# TMC2660-test.net
KiCad netlist of a schematic drawn in EAGLE
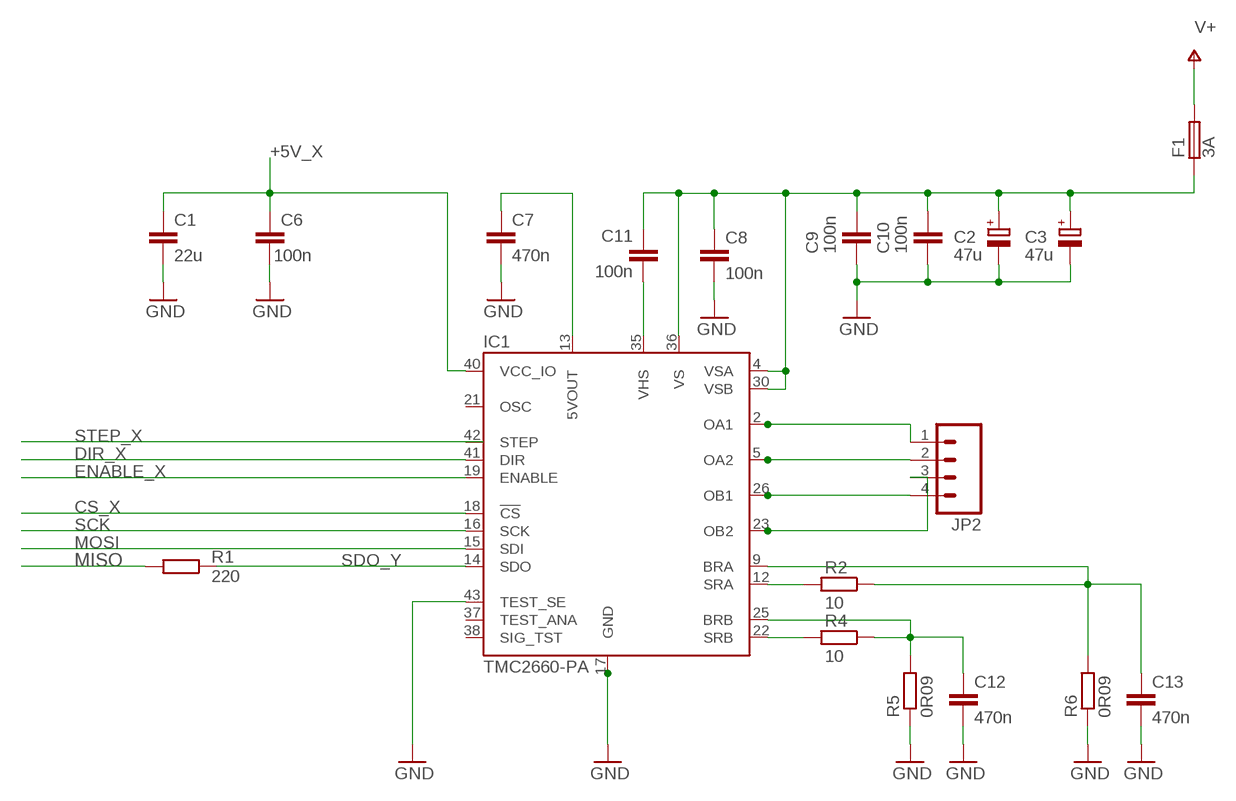
[diagram p0: schematic, sheet 1]
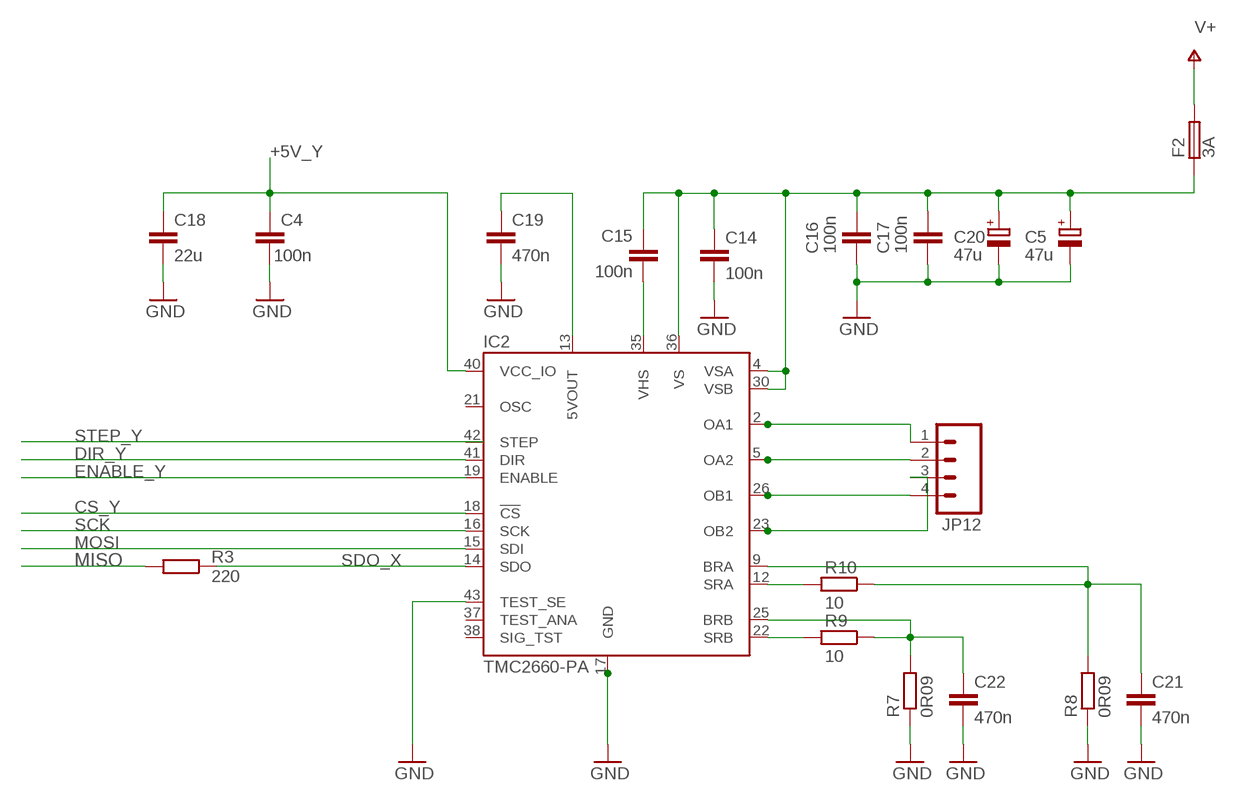
[diagram p1: schematic, sheet 2]
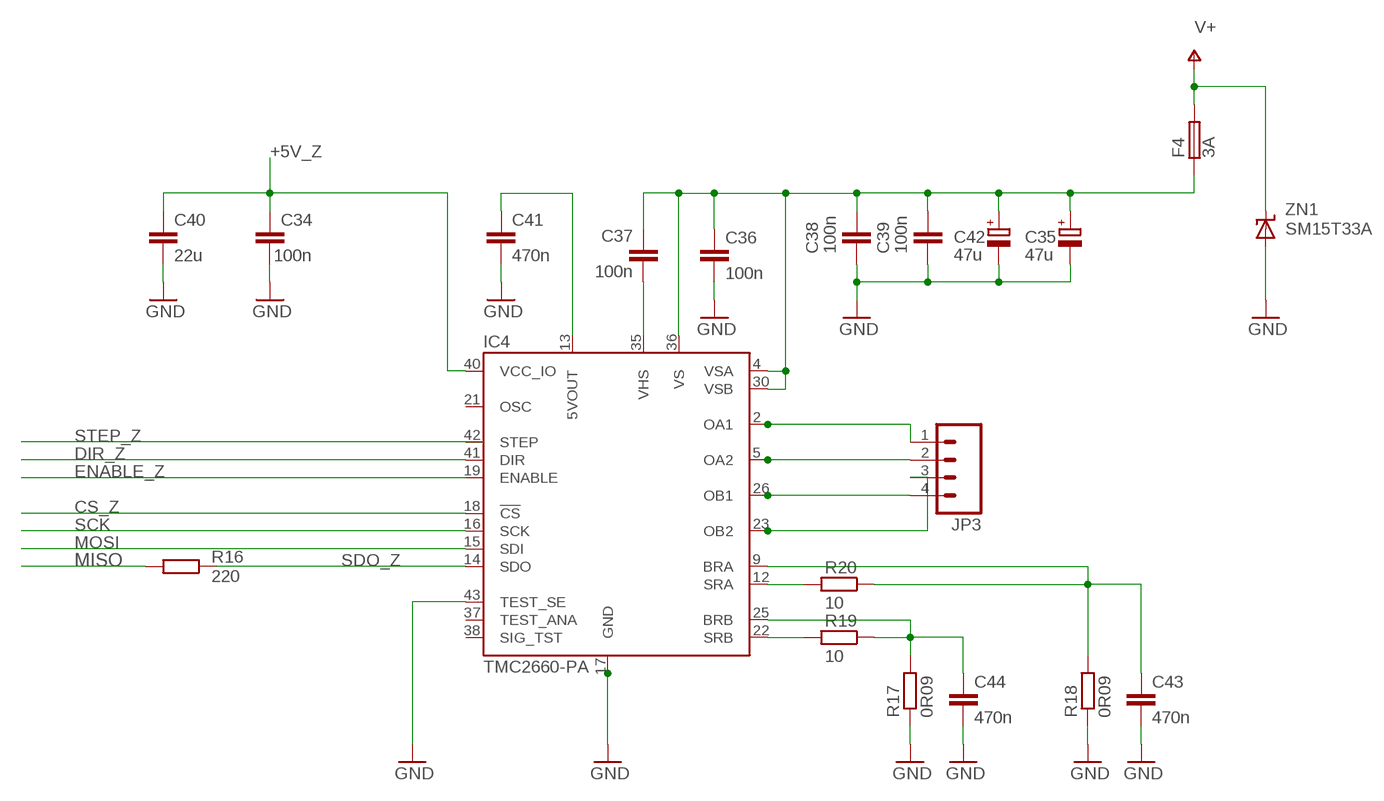
[diagram p2: schematic, sheet 3]
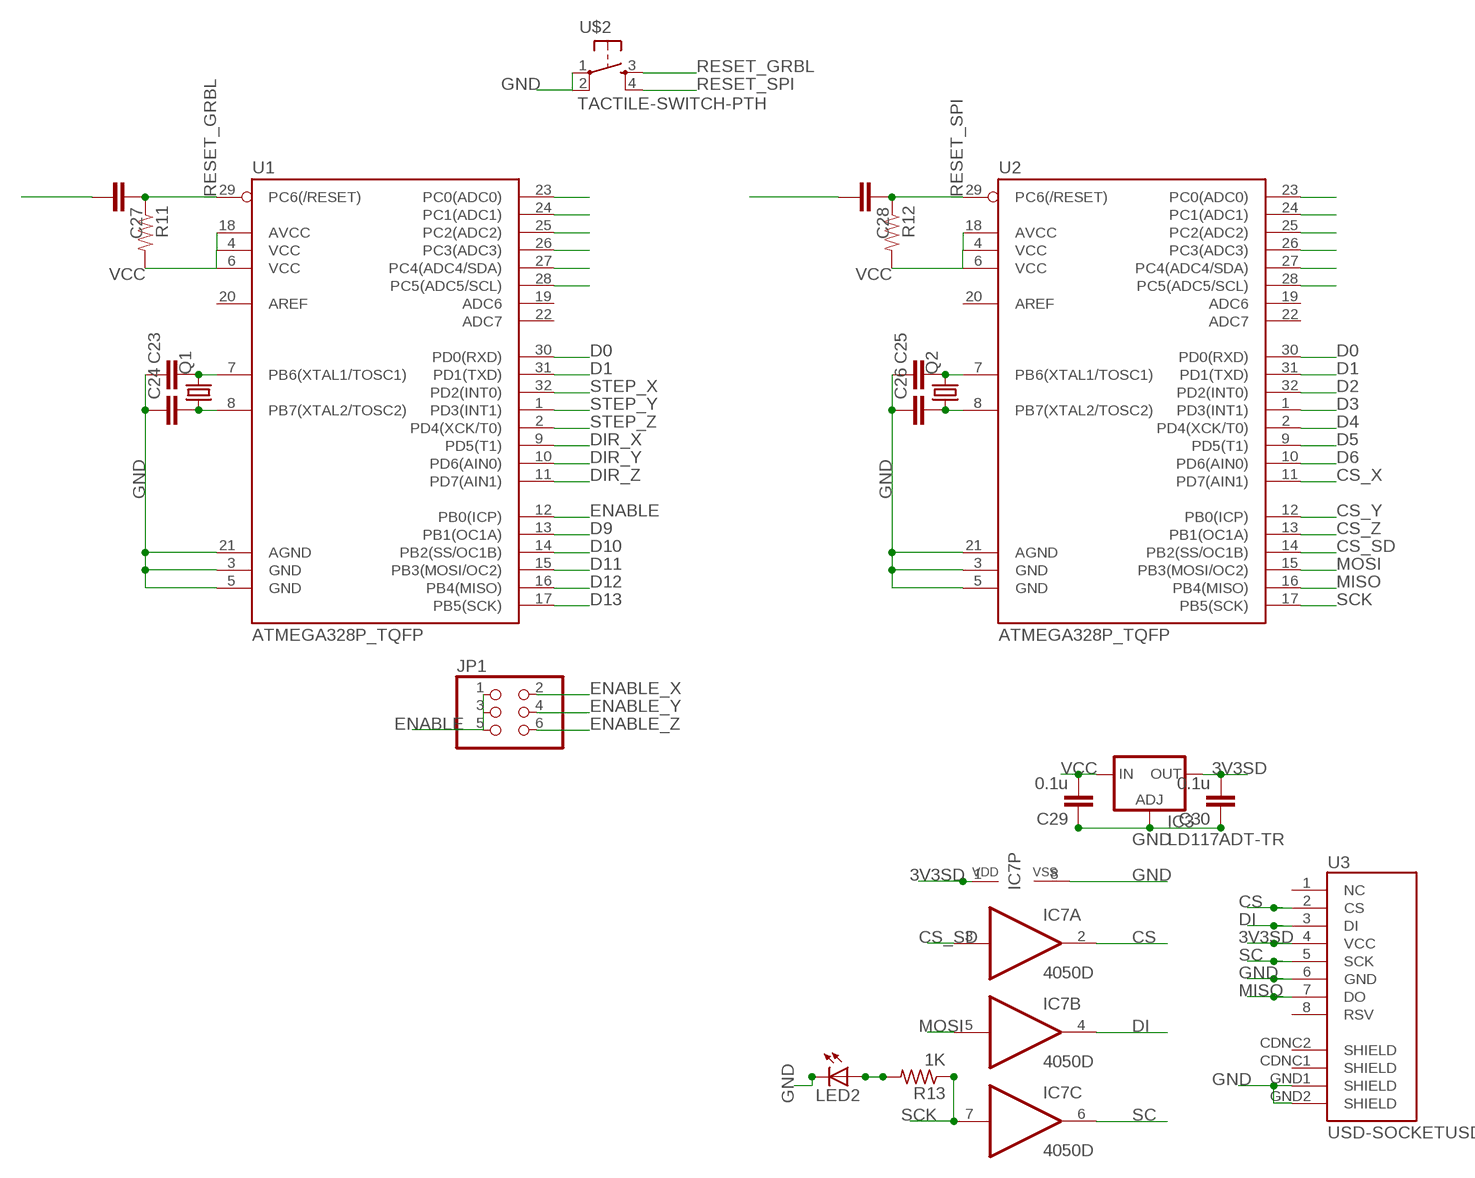
[diagram p3: schematic, sheet 4]

(export (version "E")
  (design (tool "Eeschema 10.0.6"))
  (components
    (comp (ref "C23")
      (value "CAP1206")
      (footprint "eagle-import:1206")
      (libsource (lib "eagle-import") (part "CAP1206"))
    )
    (comp (ref "C24")
      (value "CAP1206")
      (footprint "eagle-import:1206")
      (libsource (lib "eagle-import") (part "CAP1206"))
    )
    (comp (ref "C25")
      (value "CAP1206")
      (footprint "eagle-import:1206")
      (libsource (lib "eagle-import") (part "CAP1206"))
    )
    (comp (ref "C26")
      (value "CAP1206")
      (footprint "eagle-import:1206")
      (libsource (lib "eagle-import") (part "CAP1206"))
    )
    (comp (ref "C27")
      (value "CAP1206")
      (footprint "eagle-import:1206")
      (libsource (lib "eagle-import") (part "CAP1206"))
    )
    (comp (ref "C28")
      (value "CAP1206")
      (footprint "eagle-import:1206")
      (libsource (lib "eagle-import") (part "CAP1206"))
    )
    (comp (ref "C29")
      (value "0.1u")
      (footprint "eagle-import:1206")
      (libsource (lib "eagle-import") (part "SparkFun-Passives_CAP1206"))
    )
    (comp (ref "C30")
      (value "0.1u")
      (footprint "eagle-import:1206")
      (libsource (lib "eagle-import") (part "SparkFun-Passives_CAP1206"))
    )
    (comp (ref "IC3")
      (value "LD117ADT-TR")
      (footprint "eagle-import:DPACK")
      (libsource (lib "eagle-import") (part "LD117A?DT-TR"))
    )
    (comp (ref "IC7")
      (value "4050D")
      (footprint "eagle-import:SO16")
      (libsource (lib "eagle-import") (part "4050D"))
    )
    (comp (ref "JP1")
      (value "PINHD-2X3")
      (footprint "eagle-import:2X03")
      (libsource (lib "eagle-import") (part "PINHD-2X3"))
    )
    (comp (ref "LED2")
      (value "LEDSMT1206")
      (footprint "eagle-import:1206")
      (libsource (lib "eagle-import") (part "LEDSMT1206"))
    )
    (comp (ref "Q1")
      (value "CRYSTALHC49UP")
      (footprint "eagle-import:HC49UP")
      (libsource (lib "eagle-import") (part "CRYSTALHC49UP"))
    )
    (comp (ref "Q2")
      (value "CRYSTALHC49UP")
      (footprint "eagle-import:HC49UP")
      (libsource (lib "eagle-import") (part "CRYSTALHC49UP"))
    )
    (comp (ref "R11")
      (value "RESISTOR1206")
      (footprint "eagle-import:1206")
      (libsource (lib "eagle-import") (part "RESISTOR1206"))
    )
    (comp (ref "R12")
      (value "RESISTOR1206")
      (footprint "eagle-import:1206")
      (libsource (lib "eagle-import") (part "RESISTOR1206"))
    )
    (comp (ref "R13")
      (value "1K")
      (footprint "eagle-import:M1206")
      (libsource (lib "eagle-import") (part "R-US_M1206"))
    )
    (comp (ref "U$2")
      (value "TACTILE-SWITCH-PTH")
      (footprint "eagle-import:TAC-SWITCH-PTH")
      (libsource (lib "eagle-import") (part "TACTILE-SWITCH-PTH"))
    )
    (comp (ref "U1")
      (value "ATMEGA328P_TQFP")
      (footprint "eagle-import:TQFP32-08")
      (libsource (lib "eagle-import") (part "ATMEGA328P_TQFP"))
    )
    (comp (ref "U2")
      (value "ATMEGA328P_TQFP")
      (footprint "eagle-import:TQFP32-08")
      (libsource (lib "eagle-import") (part "ATMEGA328P_TQFP"))
    )
    (comp (ref "U3")
      (value "USD-SOCKETUSD")
      (footprint "eagle-import:USD-SOCKET-PP")
      (libsource (lib "eagle-import") (part "USD-SOCKETUSD"))
    )
    (comp (ref "C1")
      (value "22u")
      (footprint "eagle-import:C1206")
      (fields (field (name "MANUFACTURER") "Taiyo Yuden") (field (name "VOLTAGE") "6.3V"))
      (libsource (lib "eagle-import") (part "C-EUC1206"))
    )
    (comp (ref "C2")
      (value "47u")
      (footprint "eagle-import:E5-8,5")
      (fields (field (name "MANUFACTURER") "PANASONIC") (field (name "VOLTAGE") "50V"))
      (libsource (lib "eagle-import") (part "CPOL-EUE5-8.5"))
    )
    (comp (ref "C3")
      (value "47u")
      (footprint "eagle-import:E5-8,5")
      (fields (field (name "MANUFACTURER") "PANASONIC") (field (name "VOLTAGE") "50V"))
      (libsource (lib "eagle-import") (part "CPOL-EUE5-8.5"))
    )
    (comp (ref "C6")
      (value "100n")
      (footprint "eagle-import:C1206K")
      (fields (field (name "MANUFACTURER") "Kemet") (field (name "VOLTAGE") "25V"))
      (libsource (lib "eagle-import") (part "C-EUC1206K"))
    )
    (comp (ref "C7")
      (value "470n")
      (footprint "eagle-import:0805-WIDE")
      (fields (field (name "MANUFACTURER") "Vishay") (field (name "VOLTAGE") "10V"))
      (libsource (lib "eagle-import") (part "C-0805W"))
    )
    (comp (ref "C8")
      (value "100n")
      (footprint "eagle-import:C0603K")
      (fields (field (name "MANUFACTURER") "Kemet") (field (name "VOLTAGE") "50V"))
      (libsource (lib "eagle-import") (part "C-EUC0603K"))
    )
    (comp (ref "C9")
      (value "100n")
      (footprint "eagle-import:C0603K")
      (fields (field (name "MANUFACTURER") "Kemet") (field (name "VOLTAGE") "50V"))
      (libsource (lib "eagle-import") (part "C-EUC0603K"))
    )
    (comp (ref "C10")
      (value "100n")
      (footprint "eagle-import:C0603K")
      (fields (field (name "MANUFACTURER") "Kemet") (field (name "VOLTAGE") "50V"))
      (libsource (lib "eagle-import") (part "C-EUC0603K"))
    )
    (comp (ref "C11")
      (value "100n")
      (footprint "eagle-import:C0603K")
      (fields (field (name "MANUFACTURER") "Kemet") (field (name "VOLTAGE") "50V"))
      (libsource (lib "eagle-import") (part "C-EUC0603K"))
    )
    (comp (ref "C12")
      (value "470n")
      (footprint "eagle-import:0805-WIDE")
      (fields (field (name "MANUFACTURER") "Vishay") (field (name "VOLTAGE") "10V"))
      (libsource (lib "eagle-import") (part "C-0805W"))
    )
    (comp (ref "C13")
      (value "470n")
      (footprint "eagle-import:0805-WIDE")
      (fields (field (name "MANUFACTURER") "Vishay") (field (name "VOLTAGE") "10V"))
      (libsource (lib "eagle-import") (part "C-0805W"))
    )
    (comp (ref "F1")
      (value "3A")
      (footprint "eagle-import:AF2")
      (fields
        (field (name "MANUFACTURER") "AEM")
        (field (name "MANUFACTURER_1") "Cooper Bussman")
        (field (name "PARTNR") "CB61F3A-TR2")
        (field (name "VOLTAGE") "125V")
      )
      (libsource (lib "eagle-import") (part "AF2-FUSE_AF"))
    )
    (comp (ref "IC1")
      (value "TMC2660-PA")
      (footprint "eagle-import:PQFP44")
      (fields (field (name "MANUFACTURER") "TRINAMIC"))
      (libsource (lib "eagle-import") (part "TMC2660-PA"))
    )
    (comp (ref "JP2")
      (value "M04SCREW")
      (footprint "eagle-import:SCREWTERMINAL-3.5MM-4")
      (libsource (lib "eagle-import") (part "M04SCREW"))
    )
    (comp (ref "R1")
      (value "220")
      (footprint "eagle-import:R0603")
      (fields (field (name "MANUFACTURER") "KOA Speer"))
      (libsource (lib "eagle-import") (part "R-EU_R0603"))
    )
    (comp (ref "R2")
      (value "10")
      (footprint "eagle-import:R0603")
      (fields (field (name "MANUFACTURER") "KOA Speer"))
      (libsource (lib "eagle-import") (part "R-EU_R0603"))
    )
    (comp (ref "R4")
      (value "10")
      (footprint "eagle-import:R0603")
      (fields (field (name "MANUFACTURER") "KOA Speer"))
      (libsource (lib "eagle-import") (part "R-EU_R0603"))
    )
    (comp (ref "R5")
      (value "0R09")
      (footprint "eagle-import:R2512")
      (fields (field (name "MANUFACTURER") "Panasonic") (field (name "POWER") "0.75W"))
      (libsource (lib "eagle-import") (part "R-EU_R2512"))
    )
    (comp (ref "R6")
      (value "0R09")
      (footprint "eagle-import:R2512")
      (fields (field (name "MANUFACTURER") "Panasonic") (field (name "POWER") "0.75W"))
      (libsource (lib "eagle-import") (part "R-EU_R2512"))
    )
    (comp (ref "C34")
      (value "100n")
      (footprint "eagle-import:C1206K")
      (fields (field (name "MANUFACTURER") "Kemet") (field (name "VOLTAGE") "25V"))
      (libsource (lib "eagle-import") (part "C-EUC1206K"))
    )
    (comp (ref "C35")
      (value "47u")
      (footprint "eagle-import:E5-8,5")
      (fields (field (name "MANUFACTURER") "PANASONIC") (field (name "VOLTAGE") "50V"))
      (libsource (lib "eagle-import") (part "CPOL-EUE5-8.5"))
    )
    (comp (ref "C36")
      (value "100n")
      (footprint "eagle-import:C0603K")
      (fields (field (name "MANUFACTURER") "Kemet") (field (name "VOLTAGE") "50V"))
      (libsource (lib "eagle-import") (part "C-EUC0603K"))
    )
    (comp (ref "C37")
      (value "100n")
      (footprint "eagle-import:C0603K")
      (fields (field (name "MANUFACTURER") "Kemet") (field (name "VOLTAGE") "50V"))
      (libsource (lib "eagle-import") (part "C-EUC0603K"))
    )
    (comp (ref "C38")
      (value "100n")
      (footprint "eagle-import:C0603K")
      (fields (field (name "MANUFACTURER") "Kemet") (field (name "VOLTAGE") "50V"))
      (libsource (lib "eagle-import") (part "C-EUC0603K"))
    )
    (comp (ref "C39")
      (value "100n")
      (footprint "eagle-import:C0603K")
      (fields (field (name "MANUFACTURER") "Kemet") (field (name "VOLTAGE") "50V"))
      (libsource (lib "eagle-import") (part "C-EUC0603K"))
    )
    (comp (ref "C40")
      (value "22u")
      (footprint "eagle-import:C1206")
      (fields (field (name "MANUFACTURER") "Taiyo Yuden") (field (name "VOLTAGE") "6.3V"))
      (libsource (lib "eagle-import") (part "C-EUC1206"))
    )
    (comp (ref "C41")
      (value "470n")
      (footprint "eagle-import:0805-WIDE")
      (fields (field (name "MANUFACTURER") "Vishay") (field (name "VOLTAGE") "10V"))
      (libsource (lib "eagle-import") (part "C-0805W"))
    )
    (comp (ref "C42")
      (value "47u")
      (footprint "eagle-import:E5-8,5")
      (fields (field (name "MANUFACTURER") "PANASONIC") (field (name "VOLTAGE") "50V"))
      (libsource (lib "eagle-import") (part "CPOL-EUE5-8.5"))
    )
    (comp (ref "C43")
      (value "470n")
      (footprint "eagle-import:0805-WIDE")
      (fields (field (name "MANUFACTURER") "Vishay") (field (name "VOLTAGE") "10V"))
      (libsource (lib "eagle-import") (part "C-0805W"))
    )
    (comp (ref "C44")
      (value "470n")
      (footprint "eagle-import:0805-WIDE")
      (fields (field (name "MANUFACTURER") "Vishay") (field (name "VOLTAGE") "10V"))
      (libsource (lib "eagle-import") (part "C-0805W"))
    )
    (comp (ref "F4")
      (value "3A")
      (footprint "eagle-import:AF2")
      (fields
        (field (name "MANUFACTURER") "AEM")
        (field (name "MANUFACTURER_1") "Cooper Bussman")
        (field (name "PARTNR") "CB61F3A-TR2")
        (field (name "VOLTAGE") "125V")
      )
      (libsource (lib "eagle-import") (part "AF2-FUSE_AF"))
    )
    (comp (ref "IC4")
      (value "TMC2660-PA")
      (footprint "eagle-import:PQFP44")
      (fields (field (name "MANUFACTURER") "TRINAMIC"))
      (libsource (lib "eagle-import") (part "TMC2660-PA"))
    )
    (comp (ref "JP3")
      (value "M04SCREW")
      (footprint "eagle-import:SCREWTERMINAL-3.5MM-4")
      (libsource (lib "eagle-import") (part "M04SCREW"))
    )
    (comp (ref "R16")
      (value "220")
      (footprint "eagle-import:R0603")
      (fields (field (name "MANUFACTURER") "KOA Speer"))
      (libsource (lib "eagle-import") (part "R-EU_R0603"))
    )
    (comp (ref "R17")
      (value "0R09")
      (footprint "eagle-import:R2512")
      (fields (field (name "MANUFACTURER") "Panasonic") (field (name "POWER") "0.75W"))
      (libsource (lib "eagle-import") (part "R-EU_R2512"))
    )
    (comp (ref "R18")
      (value "0R09")
      (footprint "eagle-import:R2512")
      (fields (field (name "MANUFACTURER") "Panasonic") (field (name "POWER") "0.75W"))
      (libsource (lib "eagle-import") (part "R-EU_R2512"))
    )
    (comp (ref "R19")
      (value "10")
      (footprint "eagle-import:R0603")
      (fields (field (name "MANUFACTURER") "KOA Speer"))
      (libsource (lib "eagle-import") (part "R-EU_R0603"))
    )
    (comp (ref "R20")
      (value "10")
      (footprint "eagle-import:R0603")
      (fields (field (name "MANUFACTURER") "KOA Speer"))
      (libsource (lib "eagle-import") (part "R-EU_R0603"))
    )
    (comp (ref "ZN1")
      (value "SM15T33A")
      (footprint "eagle-import:SMC")
      (fields (field (name "MANUFACTURER") "ST"))
      (libsource (lib "eagle-import") (part "D-ZN_SMC"))
    )
    (comp (ref "C4")
      (value "100n")
      (footprint "eagle-import:C1206K")
      (fields (field (name "MANUFACTURER") "Kemet") (field (name "VOLTAGE") "25V"))
      (libsource (lib "eagle-import") (part "C-EUC1206K"))
    )
    (comp (ref "C5")
      (value "47u")
      (footprint "eagle-import:E5-8,5")
      (fields (field (name "MANUFACTURER") "PANASONIC") (field (name "VOLTAGE") "50V"))
      (libsource (lib "eagle-import") (part "CPOL-EUE5-8.5"))
    )
    (comp (ref "C14")
      (value "100n")
      (footprint "eagle-import:C0603K")
      (fields (field (name "MANUFACTURER") "Kemet") (field (name "VOLTAGE") "50V"))
      (libsource (lib "eagle-import") (part "C-EUC0603K"))
    )
    (comp (ref "C15")
      (value "100n")
      (footprint "eagle-import:C0603K")
      (fields (field (name "MANUFACTURER") "Kemet") (field (name "VOLTAGE") "50V"))
      (libsource (lib "eagle-import") (part "C-EUC0603K"))
    )
    (comp (ref "C16")
      (value "100n")
      (footprint "eagle-import:C0603K")
      (fields (field (name "MANUFACTURER") "Kemet") (field (name "VOLTAGE") "50V"))
      (libsource (lib "eagle-import") (part "C-EUC0603K"))
    )
    (comp (ref "C17")
      (value "100n")
      (footprint "eagle-import:C0603K")
      (fields (field (name "MANUFACTURER") "Kemet") (field (name "VOLTAGE") "50V"))
      (libsource (lib "eagle-import") (part "C-EUC0603K"))
    )
    (comp (ref "C18")
      (value "22u")
      (footprint "eagle-import:C1206")
      (fields (field (name "MANUFACTURER") "Taiyo Yuden") (field (name "VOLTAGE") "6.3V"))
      (libsource (lib "eagle-import") (part "C-EUC1206"))
    )
    (comp (ref "C19")
      (value "470n")
      (footprint "eagle-import:0805-WIDE")
      (fields (field (name "MANUFACTURER") "Vishay") (field (name "VOLTAGE") "10V"))
      (libsource (lib "eagle-import") (part "C-0805W"))
    )
    (comp (ref "C20")
      (value "47u")
      (footprint "eagle-import:E5-8,5")
      (fields (field (name "MANUFACTURER") "PANASONIC") (field (name "VOLTAGE") "50V"))
      (libsource (lib "eagle-import") (part "CPOL-EUE5-8.5"))
    )
    (comp (ref "C21")
      (value "470n")
      (footprint "eagle-import:0805-WIDE")
      (fields (field (name "MANUFACTURER") "Vishay") (field (name "VOLTAGE") "10V"))
      (libsource (lib "eagle-import") (part "C-0805W"))
    )
    (comp (ref "C22")
      (value "470n")
      (footprint "eagle-import:0805-WIDE")
      (fields (field (name "MANUFACTURER") "Vishay") (field (name "VOLTAGE") "10V"))
      (libsource (lib "eagle-import") (part "C-0805W"))
    )
    (comp (ref "F2")
      (value "3A")
      (footprint "eagle-import:AF2")
      (fields
        (field (name "MANUFACTURER") "AEM")
        (field (name "MANUFACTURER_1") "Cooper Bussman")
        (field (name "PARTNR") "CB61F3A-TR2")
        (field (name "VOLTAGE") "125V")
      )
      (libsource (lib "eagle-import") (part "AF2-FUSE_AF"))
    )
    (comp (ref "IC2")
      (value "TMC2660-PA")
      (footprint "eagle-import:PQFP44")
      (fields (field (name "MANUFACTURER") "TRINAMIC"))
      (libsource (lib "eagle-import") (part "TMC2660-PA"))
    )
    (comp (ref "JP12")
      (value "M04SCREW")
      (footprint "eagle-import:SCREWTERMINAL-3.5MM-4")
      (libsource (lib "eagle-import") (part "M04SCREW"))
    )
    (comp (ref "R3")
      (value "220")
      (footprint "eagle-import:R0603")
      (fields (field (name "MANUFACTURER") "KOA Speer"))
      (libsource (lib "eagle-import") (part "R-EU_R0603"))
    )
    (comp (ref "R7")
      (value "0R09")
      (footprint "eagle-import:R2512")
      (fields (field (name "MANUFACTURER") "Panasonic") (field (name "POWER") "0.75W"))
      (libsource (lib "eagle-import") (part "R-EU_R2512"))
    )
    (comp (ref "R8")
      (value "0R09")
      (footprint "eagle-import:R2512")
      (fields (field (name "MANUFACTURER") "Panasonic") (field (name "POWER") "0.75W"))
      (libsource (lib "eagle-import") (part "R-EU_R2512"))
    )
    (comp (ref "R9")
      (value "10")
      (footprint "eagle-import:R0603")
      (fields (field (name "MANUFACTURER") "KOA Speer"))
      (libsource (lib "eagle-import") (part "R-EU_R0603"))
    )
    (comp (ref "R10")
      (value "10")
      (footprint "eagle-import:R0603")
      (fields (field (name "MANUFACTURER") "KOA Speer"))
      (libsource (lib "eagle-import") (part "R-EU_R0603"))
    )
  )
  (nets
    (net (code "1") (name "+5V_X") (class "Default")
      (node (ref "C1") (pin "1") (pinfunction "1_1") (pintype "passive"))
      (node (ref "C6") (pin "2") (pinfunction "2_2") (pintype "passive"))
      (node (ref "IC1") (pin "40") (pinfunction "VCC_IO_40") (pintype "bidirectional"))
    )
    (net (code "2") (name "+5V_Y") (class "Default")
      (node (ref "C18") (pin "1") (pinfunction "1_1") (pintype "passive"))
      (node (ref "C4") (pin "2") (pinfunction "2_2") (pintype "passive"))
      (node (ref "IC2") (pin "40") (pinfunction "VCC_IO_40") (pintype "bidirectional"))
    )
    (net (code "3") (name "+5V_Z") (class "Default")
      (node (ref "C34") (pin "2") (pinfunction "2_2") (pintype "passive"))
      (node (ref "C40") (pin "1") (pinfunction "1_1") (pintype "passive"))
      (node (ref "IC4") (pin "40") (pinfunction "VCC_IO_40") (pintype "bidirectional"))
    )
    (net (code "4") (name "3V3SD") (class "Default")
      (node (ref "C30") (pin "2") (pinfunction "2_2") (pintype "passive"))
      (node (ref "IC3") (pin "4") (pinfunction "OUT_4") (pintype "passive"))
      (node (ref "IC7") (pin "1") (pinfunction "VDD_1") (pintype "power_in"))
      (node (ref "U3") (pin "4") (pinfunction "VCC_4") (pintype "bidirectional"))
    )
    (net (code "5") (name "CS") (class "Default")
      (node (ref "IC7") (pin "2") (pinfunction "O_2") (pintype "output"))
      (node (ref "U3") (pin "2") (pinfunction "CS_2") (pintype "bidirectional"))
    )
    (net (code "6") (name "CS_SD") (class "Default")
      (node (ref "IC7") (pin "3") (pinfunction "I_3") (pintype "input"))
      (node (ref "U2") (pin "14") (pinfunction "PB2(SS/OC1B)_14") (pintype "bidirectional"))
    )
    (net (code "7") (name "CS_X") (class "Default")
      (node (ref "IC1") (pin "18") (pinfunction "~{CS}_18") (pintype "bidirectional"))
      (node (ref "U2") (pin "11") (pinfunction "PD7(AIN1)_11") (pintype "bidirectional"))
    )
    (net (code "8") (name "CS_Y") (class "Default")
      (node (ref "IC2") (pin "18") (pinfunction "~{CS}_18") (pintype "bidirectional"))
      (node (ref "U2") (pin "12") (pinfunction "PB0(ICP)_12") (pintype "bidirectional"))
    )
    (net (code "9") (name "CS_Z") (class "Default")
      (node (ref "IC4") (pin "18") (pinfunction "~{CS}_18") (pintype "bidirectional"))
      (node (ref "U2") (pin "13") (pinfunction "PB1(OC1A)_13") (pintype "bidirectional"))
    )
    (net (code "10") (name "D0") (class "Default")
      (node (ref "U1") (pin "30") (pinfunction "PD0(RXD)_30") (pintype "bidirectional"))
      (node (ref "U2") (pin "30") (pinfunction "PD0(RXD)_30") (pintype "bidirectional"))
    )
    (net (code "11") (name "D1") (class "Default")
      (node (ref "U1") (pin "31") (pinfunction "PD1(TXD)_31") (pintype "bidirectional"))
      (node (ref "U2") (pin "31") (pinfunction "PD1(TXD)_31") (pintype "bidirectional"))
    )
    (net (code "12") (name "D2") (class "Default")
      (node (ref "U2") (pin "32") (pinfunction "PD2(INT0)_32") (pintype "bidirectional"))
    )
    (net (code "13") (name "D3") (class "Default")
      (node (ref "U2") (pin "1") (pinfunction "PD3(INT1)_1") (pintype "bidirectional"))
    )
    (net (code "14") (name "D4") (class "Default")
      (node (ref "U2") (pin "2") (pinfunction "PD4(XCK/T0)_2") (pintype "bidirectional"))
    )
    (net (code "15") (name "D5") (class "Default")
      (node (ref "U2") (pin "9") (pinfunction "PD5(T1)_9") (pintype "bidirectional"))
    )
    (net (code "16") (name "D6") (class "Default")
      (node (ref "U2") (pin "10") (pinfunction "PD6(AIN0)_10") (pintype "bidirectional"))
    )
    (net (code "17") (name "D9") (class "Default")
      (node (ref "U1") (pin "13") (pinfunction "PB1(OC1A)_13") (pintype "bidirectional"))
    )
    (net (code "18") (name "D10") (class "Default")
      (node (ref "U1") (pin "14") (pinfunction "PB2(SS/OC1B)_14") (pintype "bidirectional"))
    )
    (net (code "19") (name "D11") (class "Default")
      (node (ref "U1") (pin "15") (pinfunction "PB3(MOSI/OC2)_15") (pintype "bidirectional"))
    )
    (net (code "20") (name "D12") (class "Default")
      (node (ref "U1") (pin "16") (pinfunction "PB4(MISO)_16") (pintype "bidirectional"))
    )
    (net (code "21") (name "D13") (class "Default")
      (node (ref "U1") (pin "17") (pinfunction "PB5(SCK)_17") (pintype "bidirectional"))
    )
    (net (code "22") (name "DI") (class "Default")
      (node (ref "IC7") (pin "4") (pinfunction "O_4") (pintype "output"))
      (node (ref "U3") (pin "3") (pinfunction "DI_3") (pintype "bidirectional"))
    )
    (net (code "23") (name "DIR_X") (class "Default")
      (node (ref "IC1") (pin "41") (pinfunction "DIR_41") (pintype "bidirectional"))
      (node (ref "U1") (pin "9") (pinfunction "PD5(T1)_9") (pintype "bidirectional"))
    )
    (net (code "24") (name "DIR_Y") (class "Default")
      (node (ref "IC2") (pin "41") (pinfunction "DIR_41") (pintype "bidirectional"))
      (node (ref "U1") (pin "10") (pinfunction "PD6(AIN0)_10") (pintype "bidirectional"))
    )
    (net (code "25") (name "DIR_Z") (class "Default")
      (node (ref "IC4") (pin "41") (pinfunction "DIR_41") (pintype "bidirectional"))
      (node (ref "U1") (pin "11") (pinfunction "PD7(AIN1)_11") (pintype "bidirectional"))
    )
    (net (code "26") (name "ENABLE") (class "Default")
      (node (ref "JP1") (pin "1") (pinfunction "1_1") (pintype "passive"))
      (node (ref "JP1") (pin "3") (pinfunction "3_3") (pintype "passive"))
      (node (ref "JP1") (pin "5") (pinfunction "5_5") (pintype "passive"))
      (node (ref "U1") (pin "12") (pinfunction "PB0(ICP)_12") (pintype "bidirectional"))
    )
    (net (code "27") (name "ENABLE_X") (class "Default")
      (node (ref "IC1") (pin "19") (pinfunction "ENABLE_19") (pintype "bidirectional"))
      (node (ref "JP1") (pin "2") (pinfunction "2_2") (pintype "passive"))
    )
    (net (code "28") (name "ENABLE_Y") (class "Default")
      (node (ref "IC2") (pin "19") (pinfunction "ENABLE_19") (pintype "bidirectional"))
      (node (ref "JP1") (pin "4") (pinfunction "4_4") (pintype "passive"))
    )
    (net (code "29") (name "ENABLE_Z") (class "Default")
      (node (ref "IC4") (pin "19") (pinfunction "ENABLE_19") (pintype "bidirectional"))
      (node (ref "JP1") (pin "6") (pinfunction "6_6") (pintype "passive"))
    )
    (net (code "30") (name "GND") (class "Default")
      (node (ref "C1") (pin "2") (pinfunction "2_2") (pintype "passive"))
      (node (ref "C10") (pin "1") (pinfunction "1_1") (pintype "passive"))
      (node (ref "C12") (pin "2") (pinfunction "2_2") (pintype "passive"))
      (node (ref "C13") (pin "2") (pinfunction "2_2") (pintype "passive"))
      (node (ref "C14") (pin "2") (pinfunction "2_2") (pintype "passive"))
      (node (ref "C16") (pin "1") (pinfunction "1_1") (pintype "passive"))
      (node (ref "C17") (pin "1") (pinfunction "1_1") (pintype "passive"))
      (node (ref "C18") (pin "2") (pinfunction "2_2") (pintype "passive"))
      (node (ref "C19") (pin "2") (pinfunction "2_2") (pintype "passive"))
      (node (ref "C2") (pin "-") (pinfunction "-_-") (pintype "passive"))
      (node (ref "C20") (pin "-") (pinfunction "-_-") (pintype "passive"))
      (node (ref "C21") (pin "2") (pinfunction "2_2") (pintype "passive"))
      (node (ref "C22") (pin "2") (pinfunction "2_2") (pintype "passive"))
      (node (ref "C23") (pin "1") (pinfunction "1_1") (pintype "passive"))
      (node (ref "C24") (pin "1") (pinfunction "1_1") (pintype "passive"))
      (node (ref "C25") (pin "1") (pinfunction "1_1") (pintype "passive"))
      (node (ref "C26") (pin "1") (pinfunction "1_1") (pintype "passive"))
      (node (ref "C29") (pin "1") (pinfunction "1_1") (pintype "passive"))
      (node (ref "C3") (pin "-") (pinfunction "-_-") (pintype "passive"))
      (node (ref "C30") (pin "1") (pinfunction "1_1") (pintype "passive"))
      (node (ref "C34") (pin "1") (pinfunction "1_1") (pintype "passive"))
      (node (ref "C35") (pin "-") (pinfunction "-_-") (pintype "passive"))
      (node (ref "C36") (pin "2") (pinfunction "2_2") (pintype "passive"))
      (node (ref "C38") (pin "1") (pinfunction "1_1") (pintype "passive"))
      (node (ref "C39") (pin "1") (pinfunction "1_1") (pintype "passive"))
      (node (ref "C4") (pin "1") (pinfunction "1_1") (pintype "passive"))
      (node (ref "C40") (pin "2") (pinfunction "2_2") (pintype "passive"))
      (node (ref "C41") (pin "2") (pinfunction "2_2") (pintype "passive"))
      (node (ref "C42") (pin "-") (pinfunction "-_-") (pintype "passive"))
      (node (ref "C43") (pin "2") (pinfunction "2_2") (pintype "passive"))
      (node (ref "C44") (pin "2") (pinfunction "2_2") (pintype "passive"))
      (node (ref "C5") (pin "-") (pinfunction "-_-") (pintype "passive"))
      (node (ref "C6") (pin "1") (pinfunction "1_1") (pintype "passive"))
      (node (ref "C7") (pin "2") (pinfunction "2_2") (pintype "passive"))
      (node (ref "C8") (pin "2") (pinfunction "2_2") (pintype "passive"))
      (node (ref "C9") (pin "1") (pinfunction "1_1") (pintype "passive"))
      (node (ref "IC1") (pin "17") (pinfunction "GND_17") (pintype "bidirectional"))
      (node (ref "IC1") (pin "39") (pinfunction "GND1_39") (pintype "bidirectional"))
      (node (ref "IC1") (pin "43") (pinfunction "TEST_SE_43") (pintype "bidirectional"))
      (node (ref "IC1") (pin "44") (pinfunction "GND2_44") (pintype "bidirectional"))
      (node (ref "IC2") (pin "17") (pinfunction "GND_17") (pintype "bidirectional"))
      (node (ref "IC2") (pin "39") (pinfunction "GND1_39") (pintype "bidirectional"))
      (node (ref "IC2") (pin "43") (pinfunction "TEST_SE_43") (pintype "bidirectional"))
      (node (ref "IC2") (pin "44") (pinfunction "GND2_44") (pintype "bidirectional"))
      (node (ref "IC3") (pin "1") (pinfunction "ADJ_1") (pintype "input"))
      (node (ref "IC4") (pin "17") (pinfunction "GND_17") (pintype "bidirectional"))
      (node (ref "IC4") (pin "39") (pinfunction "GND1_39") (pintype "bidirectional"))
      (node (ref "IC4") (pin "43") (pinfunction "TEST_SE_43") (pintype "bidirectional"))
      (node (ref "IC4") (pin "44") (pinfunction "GND2_44") (pintype "bidirectional"))
      (node (ref "IC7") (pin "8") (pinfunction "VSS_8") (pintype "power_in"))
      (node (ref "LED2") (pin "C") (pinfunction "C_C") (pintype "passive"))
      (node (ref "R17") (pin "1") (pinfunction "1_1") (pintype "passive"))
      (node (ref "R18") (pin "1") (pinfunction "1_1") (pintype "passive"))
      (node (ref "R5") (pin "1") (pinfunction "1_1") (pintype "passive"))
      (node (ref "R6") (pin "1") (pinfunction "1_1") (pintype "passive"))
      (node (ref "R7") (pin "1") (pinfunction "1_1") (pintype "passive"))
      (node (ref "R8") (pin "1") (pinfunction "1_1") (pintype "passive"))
      (node (ref "U$2") (pin "1") (pinfunction "1_1") (pintype "passive"))
      (node (ref "U$2") (pin "2") (pinfunction "2_2") (pintype "passive"))
      (node (ref "U1") (pin "21") (pinfunction "AGND_21") (pintype "bidirectional"))
      (node (ref "U1") (pin "3") (pinfunction "GND_3") (pintype "bidirectional"))
      (node (ref "U1") (pin "5") (pinfunction "GND_5") (pintype "bidirectional"))
      (node (ref "U2") (pin "21") (pinfunction "AGND_21") (pintype "bidirectional"))
      (node (ref "U2") (pin "3") (pinfunction "GND_3") (pintype "bidirectional"))
      (node (ref "U2") (pin "5") (pinfunction "GND_5") (pintype "bidirectional"))
      (node (ref "U3") (pin "6") (pinfunction "GND_6") (pintype "bidirectional"))
      (node (ref "U3") (pin "GND1") (pinfunction "SHIELD_GND1") (pintype "bidirectional"))
      (node (ref "U3") (pin "GND2") (pinfunction "SHIELD_GND2") (pintype "bidirectional"))
      (node (ref "ZN1") (pin "P$2") (pinfunction "A_P$2") (pintype "passive"))
    )
    (net (code "31") (name "MISO") (class "Default")
      (node (ref "R1") (pin "2") (pinfunction "2_2") (pintype "passive"))
      (node (ref "R16") (pin "2") (pinfunction "2_2") (pintype "passive"))
      (node (ref "R3") (pin "2") (pinfunction "2_2") (pintype "passive"))
      (node (ref "U2") (pin "16") (pinfunction "PB4(MISO)_16") (pintype "bidirectional"))
      (node (ref "U3") (pin "7") (pinfunction "DO_7") (pintype "bidirectional"))
    )
    (net (code "32") (name "MOSI") (class "Default")
      (node (ref "IC1") (pin "15") (pinfunction "SDI_15") (pintype "bidirectional"))
      (node (ref "IC2") (pin "15") (pinfunction "SDI_15") (pintype "bidirectional"))
      (node (ref "IC4") (pin "15") (pinfunction "SDI_15") (pintype "bidirectional"))
      (node (ref "IC7") (pin "5") (pinfunction "I_5") (pintype "input"))
      (node (ref "U2") (pin "15") (pinfunction "PB3(MOSI/OC2)_15") (pintype "bidirectional"))
    )
    (net (code "33") (name "Net-(F1-1)") (class "Default")
      (node (ref "C10") (pin "2") (pinfunction "2_2") (pintype "passive"))
      (node (ref "C11") (pin "2") (pinfunction "2_2") (pintype "passive"))
      (node (ref "C2") (pin "+") (pinfunction "+_+") (pintype "passive"))
      (node (ref "C3") (pin "+") (pinfunction "+_+") (pintype "passive"))
      (node (ref "C8") (pin "1") (pinfunction "1_1") (pintype "passive"))
      (node (ref "C9") (pin "2") (pinfunction "2_2") (pintype "passive"))
      (node (ref "F1") (pin "P$1") (pinfunction "1_P$1") (pintype "passive"))
      (node (ref "IC1") (pin "30") (pinfunction "VSB_30") (pintype "bidirectional"))
      (node (ref "IC1") (pin "36") (pinfunction "VS_36") (pintype "bidirectional"))
      (node (ref "IC1") (pin "4") (pinfunction "VSA_4") (pintype "bidirectional"))
    )
    (net (code "34") (name "Net-(F2-1)") (class "Default")
      (node (ref "C14") (pin "1") (pinfunction "1_1") (pintype "passive"))
      (node (ref "C15") (pin "2") (pinfunction "2_2") (pintype "passive"))
      (node (ref "C16") (pin "2") (pinfunction "2_2") (pintype "passive"))
      (node (ref "C17") (pin "2") (pinfunction "2_2") (pintype "passive"))
      (node (ref "C20") (pin "+") (pinfunction "+_+") (pintype "passive"))
      (node (ref "C5") (pin "+") (pinfunction "+_+") (pintype "passive"))
      (node (ref "F2") (pin "P$1") (pinfunction "1_P$1") (pintype "passive"))
      (node (ref "IC2") (pin "30") (pinfunction "VSB_30") (pintype "bidirectional"))
      (node (ref "IC2") (pin "36") (pinfunction "VS_36") (pintype "bidirectional"))
      (node (ref "IC2") (pin "4") (pinfunction "VSA_4") (pintype "bidirectional"))
    )
    (net (code "35") (name "Net-(F4-1)") (class "Default")
      (node (ref "C35") (pin "+") (pinfunction "+_+") (pintype "passive"))
      (node (ref "C36") (pin "1") (pinfunction "1_1") (pintype "passive"))
      (node (ref "C37") (pin "2") (pinfunction "2_2") (pintype "passive"))
      (node (ref "C38") (pin "2") (pinfunction "2_2") (pintype "passive"))
      (node (ref "C39") (pin "2") (pinfunction "2_2") (pintype "passive"))
      (node (ref "C42") (pin "+") (pinfunction "+_+") (pintype "passive"))
      (node (ref "F4") (pin "P$1") (pinfunction "1_P$1") (pintype "passive"))
      (node (ref "IC4") (pin "30") (pinfunction "VSB_30") (pintype "bidirectional"))
      (node (ref "IC4") (pin "36") (pinfunction "VS_36") (pintype "bidirectional"))
      (node (ref "IC4") (pin "4") (pinfunction "VSA_4") (pintype "bidirectional"))
    )
    (net (code "36") (name "Net-(IC1-5VOUT)") (class "Default")
      (node (ref "C7") (pin "1") (pinfunction "1_1") (pintype "passive"))
      (node (ref "IC1") (pin "13") (pinfunction "5VOUT_13") (pintype "bidirectional"))
    )
    (net (code "37") (name "Net-(IC1-BRA)") (class "Default")
      (node (ref "C13") (pin "1") (pinfunction "1_1") (pintype "passive"))
      (node (ref "IC1") (pin "9") (pinfunction "BRA_9") (pintype "bidirectional"))
      (node (ref "R2") (pin "1") (pinfunction "1_1") (pintype "passive"))
      (node (ref "R6") (pin "2") (pinfunction "2_2") (pintype "passive"))
    )
    (net (code "38") (name "Net-(IC1-BRB)") (class "Default")
      (node (ref "C12") (pin "1") (pinfunction "1_1") (pintype "passive"))
      (node (ref "IC1") (pin "25") (pinfunction "BRB_25") (pintype "bidirectional"))
      (node (ref "R4") (pin "1") (pinfunction "1_1") (pintype "passive"))
      (node (ref "R5") (pin "2") (pinfunction "2_2") (pintype "passive"))
    )
    (net (code "39") (name "Net-(IC1-OA1)") (class "Default")
      (node (ref "IC1") (pin "2") (pinfunction "OA1_2") (pintype "bidirectional"))
      (node (ref "IC1") (pin "3") (pinfunction "OA1_1_3") (pintype "bidirectional"))
      (node (ref "IC1") (pin "7") (pinfunction "OA1_2_7") (pintype "bidirectional"))
      (node (ref "IC1") (pin "8") (pinfunction "OA1_3_8") (pintype "bidirectional"))
      (node (ref "JP2") (pin "1") (pinfunction "1_1") (pintype "passive"))
    )
    (net (code "40") (name "Net-(IC1-OA2)") (class "Default")
      (node (ref "IC1") (pin "10") (pinfunction "OA2_2_10") (pintype "bidirectional"))
      (node (ref "IC1") (pin "11") (pinfunction "OA2_3_11") (pintype "bidirectional"))
      (node (ref "IC1") (pin "5") (pinfunction "OA2_5") (pintype "bidirectional"))
      (node (ref "IC1") (pin "6") (pinfunction "OA2_1_6") (pintype "bidirectional"))
      (node (ref "JP2") (pin "2") (pinfunction "2_2") (pintype "passive"))
    )
    (net (code "41") (name "Net-(IC1-OB1)") (class "Default")
      (node (ref "IC1") (pin "26") (pinfunction "OB1_26") (pintype "bidirectional"))
      (node (ref "IC1") (pin "27") (pinfunction "OB1_1_27") (pintype "bidirectional"))
      (node (ref "IC1") (pin "31") (pinfunction "OB1_2_31") (pintype "bidirectional"))
      (node (ref "IC1") (pin "32") (pinfunction "OB1_3_32") (pintype "bidirectional"))
      (node (ref "JP2") (pin "4") (pinfunction "4_4") (pintype "passive"))
    )
    (net (code "42") (name "Net-(IC1-OB2)") (class "Default")
      (node (ref "IC1") (pin "23") (pinfunction "OB2_23") (pintype "bidirectional"))
      (node (ref "IC1") (pin "24") (pinfunction "OB2_1_24") (pintype "bidirectional"))
      (node (ref "IC1") (pin "28") (pinfunction "OB2_2_28") (pintype "bidirectional"))
      (node (ref "IC1") (pin "29") (pinfunction "OB2_3_29") (pintype "bidirectional"))
      (node (ref "JP2") (pin "3") (pinfunction "3_3") (pintype "passive"))
    )
    (net (code "43") (name "Net-(IC1-SRA)") (class "Default")
      (node (ref "IC1") (pin "12") (pinfunction "SRA_12") (pintype "bidirectional"))
      (node (ref "R2") (pin "2") (pinfunction "2_2") (pintype "passive"))
    )
    (net (code "44") (name "Net-(IC1-SRB)") (class "Default")
      (node (ref "IC1") (pin "22") (pinfunction "SRB_22") (pintype "bidirectional"))
      (node (ref "R4") (pin "2") (pinfunction "2_2") (pintype "passive"))
    )
    (net (code "45") (name "Net-(IC1-VHS)") (class "Default")
      (node (ref "C11") (pin "1") (pinfunction "1_1") (pintype "passive"))
      (node (ref "IC1") (pin "35") (pinfunction "VHS_35") (pintype "bidirectional"))
    )
    (net (code "46") (name "Net-(IC2-5VOUT)") (class "Default")
      (node (ref "C19") (pin "1") (pinfunction "1_1") (pintype "passive"))
      (node (ref "IC2") (pin "13") (pinfunction "5VOUT_13") (pintype "bidirectional"))
    )
    (net (code "47") (name "Net-(IC2-BRA)") (class "Default")
      (node (ref "C21") (pin "1") (pinfunction "1_1") (pintype "passive"))
      (node (ref "IC2") (pin "9") (pinfunction "BRA_9") (pintype "bidirectional"))
      (node (ref "R10") (pin "1") (pinfunction "1_1") (pintype "passive"))
      (node (ref "R8") (pin "2") (pinfunction "2_2") (pintype "passive"))
    )
    (net (code "48") (name "Net-(IC2-BRB)") (class "Default")
      (node (ref "C22") (pin "1") (pinfunction "1_1") (pintype "passive"))
      (node (ref "IC2") (pin "25") (pinfunction "BRB_25") (pintype "bidirectional"))
      (node (ref "R7") (pin "2") (pinfunction "2_2") (pintype "passive"))
      (node (ref "R9") (pin "1") (pinfunction "1_1") (pintype "passive"))
    )
    (net (code "49") (name "Net-(IC2-OA1)") (class "Default")
      (node (ref "IC2") (pin "2") (pinfunction "OA1_2") (pintype "bidirectional"))
      (node (ref "IC2") (pin "3") (pinfunction "OA1_1_3") (pintype "bidirectional"))
      (node (ref "IC2") (pin "7") (pinfunction "OA1_2_7") (pintype "bidirectional"))
      (node (ref "IC2") (pin "8") (pinfunction "OA1_3_8") (pintype "bidirectional"))
      (node (ref "JP12") (pin "1") (pinfunction "1_1") (pintype "passive"))
    )
    (net (code "50") (name "Net-(IC2-OA2)") (class "Default")
      (node (ref "IC2") (pin "10") (pinfunction "OA2_2_10") (pintype "bidirectional"))
      (node (ref "IC2") (pin "11") (pinfunction "OA2_3_11") (pintype "bidirectional"))
      (node (ref "IC2") (pin "5") (pinfunction "OA2_5") (pintype "bidirectional"))
      (node (ref "IC2") (pin "6") (pinfunction "OA2_1_6") (pintype "bidirectional"))
      (node (ref "JP12") (pin "2") (pinfunction "2_2") (pintype "passive"))
    )
    (net (code "51") (name "Net-(IC2-OB1)") (class "Default")
      (node (ref "IC2") (pin "26") (pinfunction "OB1_26") (pintype "bidirectional"))
      (node (ref "IC2") (pin "27") (pinfunction "OB1_1_27") (pintype "bidirectional"))
      (node (ref "IC2") (pin "31") (pinfunction "OB1_2_31") (pintype "bidirectional"))
      (node (ref "IC2") (pin "32") (pinfunction "OB1_3_32") (pintype "bidirectional"))
      (node (ref "JP12") (pin "4") (pinfunction "4_4") (pintype "passive"))
    )
    (net (code "52") (name "Net-(IC2-OB2)") (class "Default")
      (node (ref "IC2") (pin "23") (pinfunction "OB2_23") (pintype "bidirectional"))
      (node (ref "IC2") (pin "24") (pinfunction "OB2_1_24") (pintype "bidirectional"))
      (node (ref "IC2") (pin "28") (pinfunction "OB2_2_28") (pintype "bidirectional"))
      (node (ref "IC2") (pin "29") (pinfunction "OB2_3_29") (pintype "bidirectional"))
      (node (ref "JP12") (pin "3") (pinfunction "3_3") (pintype "passive"))
    )
    (net (code "53") (name "Net-(IC2-SRA)") (class "Default")
      (node (ref "IC2") (pin "12") (pinfunction "SRA_12") (pintype "bidirectional"))
      (node (ref "R10") (pin "2") (pinfunction "2_2") (pintype "passive"))
    )
    (net (code "54") (name "Net-(IC2-SRB)") (class "Default")
      (node (ref "IC2") (pin "22") (pinfunction "SRB_22") (pintype "bidirectional"))
      (node (ref "R9") (pin "2") (pinfunction "2_2") (pintype "passive"))
    )
    (net (code "55") (name "Net-(IC2-VHS)") (class "Default")
      (node (ref "C15") (pin "1") (pinfunction "1_1") (pintype "passive"))
      (node (ref "IC2") (pin "35") (pinfunction "VHS_35") (pintype "bidirectional"))
    )
    (net (code "56") (name "Net-(IC4-5VOUT)") (class "Default")
      (node (ref "C41") (pin "1") (pinfunction "1_1") (pintype "passive"))
      (node (ref "IC4") (pin "13") (pinfunction "5VOUT_13") (pintype "bidirectional"))
    )
    (net (code "57") (name "Net-(IC4-BRA)") (class "Default")
      (node (ref "C43") (pin "1") (pinfunction "1_1") (pintype "passive"))
      (node (ref "IC4") (pin "9") (pinfunction "BRA_9") (pintype "bidirectional"))
      (node (ref "R18") (pin "2") (pinfunction "2_2") (pintype "passive"))
      (node (ref "R20") (pin "1") (pinfunction "1_1") (pintype "passive"))
    )
    (net (code "58") (name "Net-(IC4-BRB)") (class "Default")
      (node (ref "C44") (pin "1") (pinfunction "1_1") (pintype "passive"))
      (node (ref "IC4") (pin "25") (pinfunction "BRB_25") (pintype "bidirectional"))
      (node (ref "R17") (pin "2") (pinfunction "2_2") (pintype "passive"))
      (node (ref "R19") (pin "1") (pinfunction "1_1") (pintype "passive"))
    )
    (net (code "59") (name "Net-(IC4-OA1)") (class "Default")
      (node (ref "IC4") (pin "2") (pinfunction "OA1_2") (pintype "bidirectional"))
      (node (ref "IC4") (pin "3") (pinfunction "OA1_1_3") (pintype "bidirectional"))
      (node (ref "IC4") (pin "7") (pinfunction "OA1_2_7") (pintype "bidirectional"))
      (node (ref "IC4") (pin "8") (pinfunction "OA1_3_8") (pintype "bidirectional"))
      (node (ref "JP3") (pin "1") (pinfunction "1_1") (pintype "passive"))
    )
    (net (code "60") (name "Net-(IC4-OA2)") (class "Default")
      (node (ref "IC4") (pin "10") (pinfunction "OA2_2_10") (pintype "bidirectional"))
      (node (ref "IC4") (pin "11") (pinfunction "OA2_3_11") (pintype "bidirectional"))
      (node (ref "IC4") (pin "5") (pinfunction "OA2_5") (pintype "bidirectional"))
      (node (ref "IC4") (pin "6") (pinfunction "OA2_1_6") (pintype "bidirectional"))
      (node (ref "JP3") (pin "2") (pinfunction "2_2") (pintype "passive"))
    )
    (net (code "61") (name "Net-(IC4-OB1)") (class "Default")
      (node (ref "IC4") (pin "26") (pinfunction "OB1_26") (pintype "bidirectional"))
      (node (ref "IC4") (pin "27") (pinfunction "OB1_1_27") (pintype "bidirectional"))
      (node (ref "IC4") (pin "31") (pinfunction "OB1_2_31") (pintype "bidirectional"))
      (node (ref "IC4") (pin "32") (pinfunction "OB1_3_32") (pintype "bidirectional"))
      (node (ref "JP3") (pin "4") (pinfunction "4_4") (pintype "passive"))
    )
    (net (code "62") (name "Net-(IC4-OB2)") (class "Default")
      (node (ref "IC4") (pin "23") (pinfunction "OB2_23") (pintype "bidirectional"))
      (node (ref "IC4") (pin "24") (pinfunction "OB2_1_24") (pintype "bidirectional"))
      (node (ref "IC4") (pin "28") (pinfunction "OB2_2_28") (pintype "bidirectional"))
      (node (ref "IC4") (pin "29") (pinfunction "OB2_3_29") (pintype "bidirectional"))
      (node (ref "JP3") (pin "3") (pinfunction "3_3") (pintype "passive"))
    )
    (net (code "63") (name "Net-(IC4-SRA)") (class "Default")
      (node (ref "IC4") (pin "12") (pinfunction "SRA_12") (pintype "bidirectional"))
      (node (ref "R20") (pin "2") (pinfunction "2_2") (pintype "passive"))
    )
    (net (code "64") (name "Net-(IC4-SRB)") (class "Default")
      (node (ref "IC4") (pin "22") (pinfunction "SRB_22") (pintype "bidirectional"))
      (node (ref "R19") (pin "2") (pinfunction "2_2") (pintype "passive"))
    )
    (net (code "65") (name "Net-(IC4-VHS)") (class "Default")
      (node (ref "C37") (pin "1") (pinfunction "1_1") (pintype "passive"))
      (node (ref "IC4") (pin "35") (pinfunction "VHS_35") (pintype "bidirectional"))
    )
    (net (code "66") (name "Net-(LED2-PadA)") (class "Default")
      (node (ref "LED2") (pin "A") (pinfunction "A_A") (pintype "passive"))
      (node (ref "R13") (pin "2") (pinfunction "2_2") (pintype "passive"))
    )
    (net (code "67") (name "Net-(U1-PB6(XTAL1{slash}TOSC1))") (class "Default")
      (node (ref "C23") (pin "2") (pinfunction "2_2") (pintype "passive"))
      (node (ref "Q1") (pin "2") (pinfunction "2_2") (pintype "passive"))
      (node (ref "U1") (pin "7") (pinfunction "PB6(XTAL1/TOSC1)_7") (pintype "bidirectional"))
    )
    (net (code "68") (name "Net-(U1-PB7(XTAL2{slash}TOSC2))") (class "Default")
      (node (ref "C24") (pin "2") (pinfunction "2_2") (pintype "passive"))
      (node (ref "Q1") (pin "1") (pinfunction "1_1") (pintype "passive"))
      (node (ref "U1") (pin "8") (pinfunction "PB7(XTAL2/TOSC2)_8") (pintype "bidirectional"))
    )
    (net (code "69") (name "Net-(U2-PB6(XTAL1{slash}TOSC1))") (class "Default")
      (node (ref "C25") (pin "2") (pinfunction "2_2") (pintype "passive"))
      (node (ref "Q2") (pin "2") (pinfunction "2_2") (pintype "passive"))
      (node (ref "U2") (pin "7") (pinfunction "PB6(XTAL1/TOSC1)_7") (pintype "bidirectional"))
    )
    (net (code "70") (name "Net-(U2-PB7(XTAL2{slash}TOSC2))") (class "Default")
      (node (ref "C26") (pin "2") (pinfunction "2_2") (pintype "passive"))
      (node (ref "Q2") (pin "1") (pinfunction "1_1") (pintype "passive"))
      (node (ref "U2") (pin "8") (pinfunction "PB7(XTAL2/TOSC2)_8") (pintype "bidirectional"))
    )
    (net (code "71") (name "RESET_GRBL") (class "Default")
      (node (ref "C27") (pin "1") (pinfunction "1_1") (pintype "passive"))
      (node (ref "R11") (pin "1") (pinfunction "1_1") (pintype "passive"))
      (node (ref "U$2") (pin "3") (pinfunction "3_3") (pintype "passive"))
      (node (ref "U1") (pin "29") (pinfunction "PC6(/RESET)_29") (pintype "bidirectional"))
    )
    (net (code "72") (name "RESET_SPI") (class "Default")
      (node (ref "C28") (pin "1") (pinfunction "1_1") (pintype "passive"))
      (node (ref "R12") (pin "1") (pinfunction "1_1") (pintype "passive"))
      (node (ref "U$2") (pin "4") (pinfunction "4_4") (pintype "passive"))
      (node (ref "U2") (pin "29") (pinfunction "PC6(/RESET)_29") (pintype "bidirectional"))
    )
    (net (code "73") (name "SC") (class "Default")
      (node (ref "IC7") (pin "6") (pinfunction "O_6") (pintype "output"))
      (node (ref "U3") (pin "5") (pinfunction "SCK_5") (pintype "bidirectional"))
    )
    (net (code "74") (name "SCK") (class "Default")
      (node (ref "IC1") (pin "16") (pinfunction "SCK_16") (pintype "bidirectional"))
      (node (ref "IC2") (pin "16") (pinfunction "SCK_16") (pintype "bidirectional"))
      (node (ref "IC4") (pin "16") (pinfunction "SCK_16") (pintype "bidirectional"))
      (node (ref "IC7") (pin "7") (pinfunction "I_7") (pintype "input"))
      (node (ref "R13") (pin "1") (pinfunction "1_1") (pintype "passive"))
      (node (ref "U2") (pin "17") (pinfunction "PB5(SCK)_17") (pintype "bidirectional"))
    )
    (net (code "75") (name "SDO_X") (class "Default")
      (node (ref "IC2") (pin "14") (pinfunction "SDO_14") (pintype "bidirectional"))
      (node (ref "R3") (pin "1") (pinfunction "1_1") (pintype "passive"))
    )
    (net (code "76") (name "SDO_Y") (class "Default")
      (node (ref "IC1") (pin "14") (pinfunction "SDO_14") (pintype "bidirectional"))
      (node (ref "R1") (pin "1") (pinfunction "1_1") (pintype "passive"))
    )
    (net (code "77") (name "SDO_Z") (class "Default")
      (node (ref "IC4") (pin "14") (pinfunction "SDO_14") (pintype "bidirectional"))
      (node (ref "R16") (pin "1") (pinfunction "1_1") (pintype "passive"))
    )
    (net (code "78") (name "STEP_X") (class "Default")
      (node (ref "IC1") (pin "42") (pinfunction "STEP_42") (pintype "bidirectional"))
      (node (ref "U1") (pin "32") (pinfunction "PD2(INT0)_32") (pintype "bidirectional"))
    )
    (net (code "79") (name "STEP_Y") (class "Default")
      (node (ref "IC2") (pin "42") (pinfunction "STEP_42") (pintype "bidirectional"))
      (node (ref "U1") (pin "1") (pinfunction "PD3(INT1)_1") (pintype "bidirectional"))
    )
    (net (code "80") (name "STEP_Z") (class "Default")
      (node (ref "IC4") (pin "42") (pinfunction "STEP_42") (pintype "bidirectional"))
      (node (ref "U1") (pin "2") (pinfunction "PD4(XCK/T0)_2") (pintype "bidirectional"))
    )
    (net (code "81") (name "V+") (class "Default")
      (node (ref "F1") (pin "P$2") (pinfunction "2_P$2") (pintype "passive"))
      (node (ref "F2") (pin "P$2") (pinfunction "2_P$2") (pintype "passive"))
      (node (ref "F4") (pin "P$2") (pinfunction "2_P$2") (pintype "passive"))
      (node (ref "ZN1") (pin "P$1") (pinfunction "C_P$1") (pintype "passive"))
    )
    (net (code "82") (name "VCC") (class "Default")
      (node (ref "C29") (pin "2") (pinfunction "2_2") (pintype "passive"))
      (node (ref "IC3") (pin "3") (pinfunction "IN_3") (pintype "input"))
      (node (ref "R11") (pin "2") (pinfunction "2_2") (pintype "passive"))
      (node (ref "R12") (pin "2") (pinfunction "2_2") (pintype "passive"))
      (node (ref "U1") (pin "18") (pinfunction "AVCC_18") (pintype "bidirectional"))
      (node (ref "U1") (pin "4") (pinfunction "VCC_4") (pintype "bidirectional"))
      (node (ref "U1") (pin "6") (pinfunction "VCC_6") (pintype "bidirectional"))
      (node (ref "U2") (pin "18") (pinfunction "AVCC_18") (pintype "bidirectional"))
      (node (ref "U2") (pin "4") (pinfunction "VCC_4") (pintype "bidirectional"))
      (node (ref "U2") (pin "6") (pinfunction "VCC_6") (pintype "bidirectional"))
    )
    (net (code "83") (name "unconnected-(C27-Pad2)") (class "Default")
      (node (ref "C27") (pin "2") (pinfunction "2_2") (pintype "passive"))
    )
    (net (code "84") (name "unconnected-(C28-Pad2)") (class "Default")
      (node (ref "C28") (pin "2") (pinfunction "2_2") (pintype "passive"))
    )
    (net (code "85") (name "unconnected-(IC1-OSC-Pad21)") (class "Default")
      (node (ref "IC1") (pin "21") (pinfunction "OSC_21") (pintype "bidirectional"))
    )
    (net (code "86") (name "unconnected-(IC1-SIG_TST-Pad38)") (class "Default")
      (node (ref "IC1") (pin "38") (pinfunction "SIG_TST_38") (pintype "bidirectional"))
    )
    (net (code "87") (name "unconnected-(IC1-TEST_ANA-Pad37)") (class "Default")
      (node (ref "IC1") (pin "37") (pinfunction "TEST_ANA_37") (pintype "bidirectional"))
    )
    (net (code "88") (name "unconnected-(IC2-OSC-Pad21)") (class "Default")
      (node (ref "IC2") (pin "21") (pinfunction "OSC_21") (pintype "bidirectional"))
    )
    (net (code "89") (name "unconnected-(IC2-SIG_TST-Pad38)") (class "Default")
      (node (ref "IC2") (pin "38") (pinfunction "SIG_TST_38") (pintype "bidirectional"))
    )
    (net (code "90") (name "unconnected-(IC2-TEST_ANA-Pad37)") (class "Default")
      (node (ref "IC2") (pin "37") (pinfunction "TEST_ANA_37") (pintype "bidirectional"))
    )
    (net (code "91") (name "unconnected-(IC4-OSC-Pad21)") (class "Default")
      (node (ref "IC4") (pin "21") (pinfunction "OSC_21") (pintype "bidirectional"))
    )
    (net (code "92") (name "unconnected-(IC4-SIG_TST-Pad38)") (class "Default")
      (node (ref "IC4") (pin "38") (pinfunction "SIG_TST_38") (pintype "bidirectional"))
    )
    (net (code "93") (name "unconnected-(IC4-TEST_ANA-Pad37)") (class "Default")
      (node (ref "IC4") (pin "37") (pinfunction "TEST_ANA_37") (pintype "bidirectional"))
    )
    (net (code "94") (name "unconnected-(U1-ADC6-Pad19)") (class "Default")
      (node (ref "U1") (pin "19") (pinfunction "ADC6_19") (pintype "bidirectional"))
    )
    (net (code "95") (name "unconnected-(U1-ADC7-Pad22)") (class "Default")
      (node (ref "U1") (pin "22") (pinfunction "ADC7_22") (pintype "bidirectional"))
    )
    (net (code "96") (name "unconnected-(U1-AREF-Pad20)") (class "Default")
      (node (ref "U1") (pin "20") (pinfunction "AREF_20") (pintype "bidirectional"))
    )
    (net (code "97") (name "unconnected-(U1-PC0(ADC0)-Pad23)") (class "Default")
      (node (ref "U1") (pin "23") (pinfunction "PC0(ADC0)_23") (pintype "bidirectional"))
    )
    (net (code "98") (name "unconnected-(U1-PC1(ADC1)-Pad24)") (class "Default")
      (node (ref "U1") (pin "24") (pinfunction "PC1(ADC1)_24") (pintype "bidirectional"))
    )
    (net (code "99") (name "unconnected-(U1-PC2(ADC2)-Pad25)") (class "Default")
      (node (ref "U1") (pin "25") (pinfunction "PC2(ADC2)_25") (pintype "bidirectional"))
    )
    (net (code "100") (name "unconnected-(U1-PC3(ADC3)-Pad26)") (class "Default")
      (node (ref "U1") (pin "26") (pinfunction "PC3(ADC3)_26") (pintype "bidirectional"))
    )
    (net (code "101") (name "unconnected-(U1-PC4(ADC4{slash}SDA)-Pad27)") (class "Default")
      (node (ref "U1") (pin "27") (pinfunction "PC4(ADC4/SDA)_27") (pintype "bidirectional"))
    )
    (net (code "102") (name "unconnected-(U1-PC5(ADC5{slash}SCL)-Pad28)") (class "Default")
      (node (ref "U1") (pin "28") (pinfunction "PC5(ADC5/SCL)_28") (pintype "bidirectional"))
    )
    (net (code "103") (name "unconnected-(U2-ADC6-Pad19)") (class "Default")
      (node (ref "U2") (pin "19") (pinfunction "ADC6_19") (pintype "bidirectional"))
    )
    (net (code "104") (name "unconnected-(U2-ADC7-Pad22)") (class "Default")
      (node (ref "U2") (pin "22") (pinfunction "ADC7_22") (pintype "bidirectional"))
    )
    (net (code "105") (name "unconnected-(U2-AREF-Pad20)") (class "Default")
      (node (ref "U2") (pin "20") (pinfunction "AREF_20") (pintype "bidirectional"))
    )
    (net (code "106") (name "unconnected-(U2-PC0(ADC0)-Pad23)") (class "Default")
      (node (ref "U2") (pin "23") (pinfunction "PC0(ADC0)_23") (pintype "bidirectional"))
    )
    (net (code "107") (name "unconnected-(U2-PC1(ADC1)-Pad24)") (class "Default")
      (node (ref "U2") (pin "24") (pinfunction "PC1(ADC1)_24") (pintype "bidirectional"))
    )
    (net (code "108") (name "unconnected-(U2-PC2(ADC2)-Pad25)") (class "Default")
      (node (ref "U2") (pin "25") (pinfunction "PC2(ADC2)_25") (pintype "bidirectional"))
    )
    (net (code "109") (name "unconnected-(U2-PC3(ADC3)-Pad26)") (class "Default")
      (node (ref "U2") (pin "26") (pinfunction "PC3(ADC3)_26") (pintype "bidirectional"))
    )
    (net (code "110") (name "unconnected-(U2-PC4(ADC4{slash}SDA)-Pad27)") (class "Default")
      (node (ref "U2") (pin "27") (pinfunction "PC4(ADC4/SDA)_27") (pintype "bidirectional"))
    )
    (net (code "111") (name "unconnected-(U2-PC5(ADC5{slash}SCL)-Pad28)") (class "Default")
      (node (ref "U2") (pin "28") (pinfunction "PC5(ADC5/SCL)_28") (pintype "bidirectional"))
    )
    (net (code "112") (name "unconnected-(U3-NC-Pad1)") (class "Default")
      (node (ref "U3") (pin "1") (pinfunction "NC_1") (pintype "bidirectional"))
    )
    (net (code "113") (name "unconnected-(U3-RSV-Pad8)") (class "Default")
      (node (ref "U3") (pin "8") (pinfunction "RSV_8") (pintype "bidirectional"))
    )
    (net (code "114") (name "unconnected-(U3-SHIELD-PadCDNC1)") (class "Default")
      (node (ref "U3") (pin "CDNC1") (pinfunction "SHIELD_CDNC1") (pintype "bidirectional"))
    )
    (net (code "115") (name "unconnected-(U3-SHIELD-PadCDNC2)") (class "Default")
      (node (ref "U3") (pin "CDNC2") (pinfunction "SHIELD_CDNC2") (pintype "bidirectional"))
    )
  )
)
